# AIO-RF-v2-Sheet1.net
KiCad netlist of a schematic drawn in Altium Designer
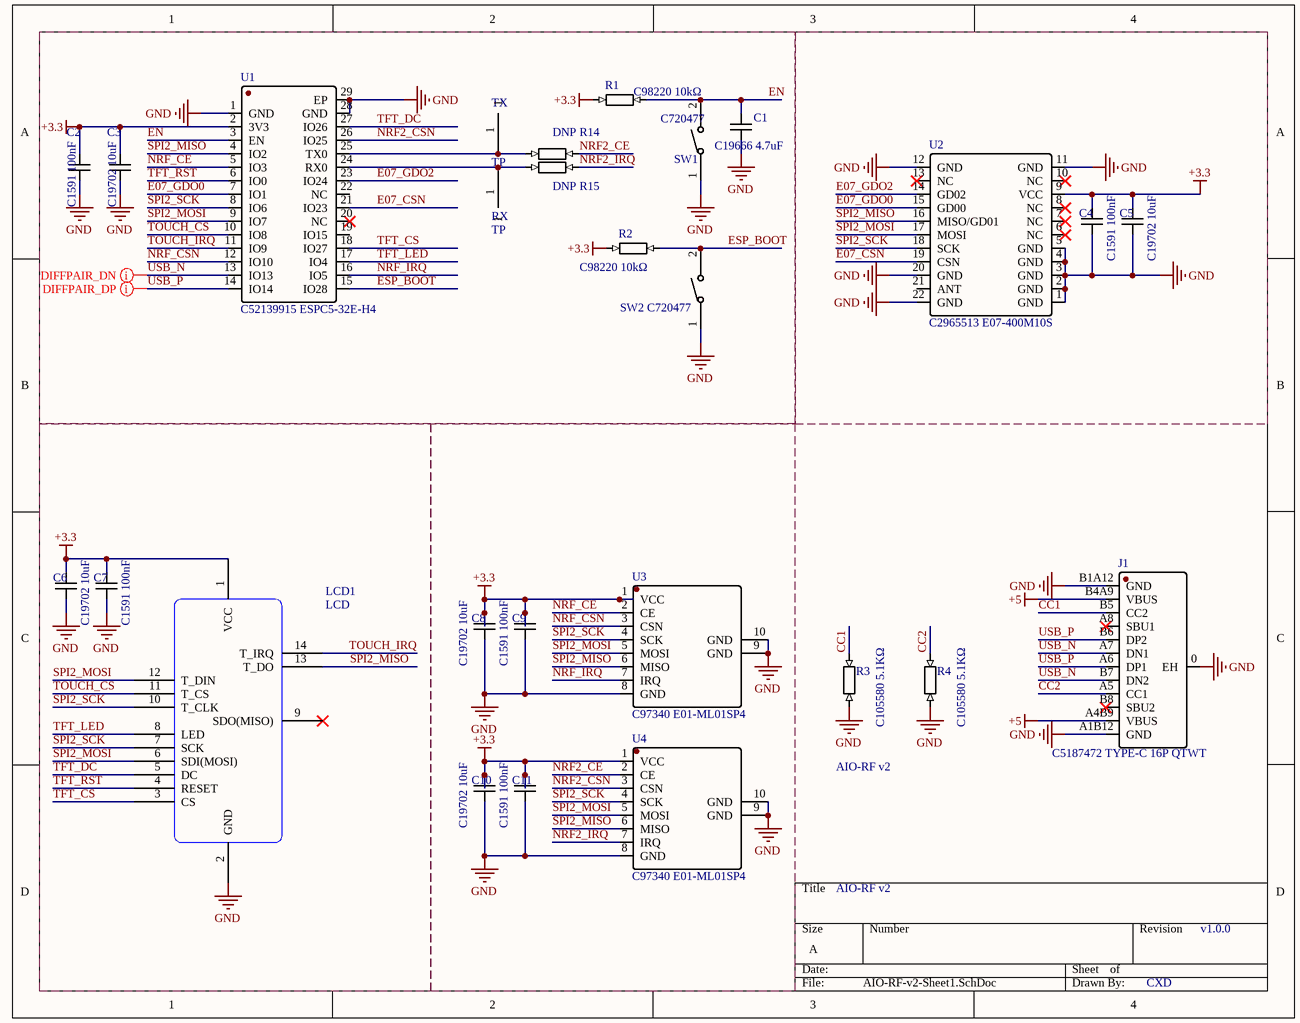
[diagram p0: AIO-RF-v2-Sheet1.SchDoc]

(export (version "E")
  (design (tool "Eeschema 10.0.6"))
  (components
    (comp (ref "C1")
      (value "C19666 4.7uF")
      (footprint "C19666")
      (description "4.7uF (475) ±10% 16V")
      (fields
        (field (name "LCSC PART NUMBER") "C19666")
        (field (name "MANUFACTURER") "SAMSUNG(三星)")
        (field (name "IMPORTED BY") "JLCAltiumImporter 0.3.1")
      )
      (libsource (lib "Schlib1") (part "C19666"))
    )
    (comp (ref "C2")
      (value "C1591 100nF")
      (footprint "C1591")
      (description "100nF (104) ±10% 50V")
      (fields
        (field (name "LCSC PART NUMBER") "C1591")
        (field (name "MANUFACTURER") "SAMSUNG(三星)")
        (field (name "IMPORTED BY") "JLCAltiumImporter 0.3.1")
      )
      (libsource (lib "Schlib1") (part "C1591"))
    )
    (comp (ref "C3")
      (value "C19702 10uF")
      (footprint "C19702")
      (fields
        (field (name "LCSC PART NUMBER") "C19702")
        (field (name "MANUFACTURER") "SAMSUNG(三星)")
        (field (name "MANUFACTURER PART NUMBER") "CL10A106KP8NNNC")
        (field (name "IMPORTED BY") "JLCAltiumImporter 0.3.1")
      )
      (libsource (lib "Schlib1") (part "C19702"))
    )
    (comp (ref "C4")
      (value "C1591 100nF")
      (footprint "C1591")
      (description "100nF (104) ±10% 50V")
      (fields
        (field (name "LCSC PART NUMBER") "C1591")
        (field (name "MANUFACTURER") "SAMSUNG(三星)")
        (field (name "IMPORTED BY") "JLCAltiumImporter 0.3.1")
      )
      (libsource (lib "Schlib1") (part "C1591"))
    )
    (comp (ref "C5")
      (value "C19702 10uF")
      (footprint "C19702")
      (fields
        (field (name "LCSC PART NUMBER") "C19702")
        (field (name "MANUFACTURER") "SAMSUNG(三星)")
        (field (name "MANUFACTURER PART NUMBER") "CL10A106KP8NNNC")
        (field (name "IMPORTED BY") "JLCAltiumImporter 0.3.1")
      )
      (libsource (lib "Schlib1") (part "C19702"))
    )
    (comp (ref "C6")
      (value "C19702 10uF")
      (footprint "C19702")
      (fields
        (field (name "LCSC PART NUMBER") "C19702")
        (field (name "MANUFACTURER") "SAMSUNG(三星)")
        (field (name "MANUFACTURER PART NUMBER") "CL10A106KP8NNNC")
        (field (name "IMPORTED BY") "JLCAltiumImporter 0.3.1")
      )
      (libsource (lib "Schlib1") (part "C19702"))
    )
    (comp (ref "C7")
      (value "C1591 100nF")
      (footprint "C1591")
      (description "100nF (104) ±10% 50V")
      (fields
        (field (name "LCSC PART NUMBER") "C1591")
        (field (name "MANUFACTURER") "SAMSUNG(三星)")
        (field (name "IMPORTED BY") "JLCAltiumImporter 0.3.1")
      )
      (libsource (lib "Schlib1") (part "C1591"))
    )
    (comp (ref "C8")
      (value "C19702 10uF")
      (footprint "C19702")
      (fields
        (field (name "LCSC PART NUMBER") "C19702")
        (field (name "MANUFACTURER") "SAMSUNG(三星)")
        (field (name "MANUFACTURER PART NUMBER") "CL10A106KP8NNNC")
        (field (name "IMPORTED BY") "JLCAltiumImporter 0.3.1")
      )
      (libsource (lib "Schlib1") (part "C19702"))
    )
    (comp (ref "C9")
      (value "C1591 100nF")
      (footprint "C1591")
      (description "100nF (104) ±10% 50V")
      (fields
        (field (name "LCSC PART NUMBER") "C1591")
        (field (name "MANUFACTURER") "SAMSUNG(三星)")
        (field (name "IMPORTED BY") "JLCAltiumImporter 0.3.1")
      )
      (libsource (lib "Schlib1") (part "C1591"))
    )
    (comp (ref "C10")
      (value "C19702 10uF")
      (footprint "C19702")
      (fields
        (field (name "LCSC PART NUMBER") "C19702")
        (field (name "MANUFACTURER") "SAMSUNG(三星)")
        (field (name "MANUFACTURER PART NUMBER") "CL10A106KP8NNNC")
        (field (name "IMPORTED BY") "JLCAltiumImporter 0.3.1")
      )
      (libsource (lib "Schlib1") (part "C19702"))
    )
    (comp (ref "C11")
      (value "C1591 100nF")
      (footprint "C1591")
      (description "100nF (104) ±10% 50V")
      (fields
        (field (name "LCSC PART NUMBER") "C1591")
        (field (name "MANUFACTURER") "SAMSUNG(三星)")
        (field (name "IMPORTED BY") "JLCAltiumImporter 0.3.1")
      )
      (libsource (lib "Schlib1") (part "C1591"))
    )
    (comp (ref "J1")
      (value "C5187472 TYPE-C 16P QTWT")
      (footprint "C5187472")
      (fields
        (field (name "LCSC PART NUMBER") "C5187472")
        (field (name "MANUFACTURER") "SHOU HAN(首韩)")
        (field (name "MANUFACTURER PART NUMBER") "TYPE-C 16P QTWT")
        (field (name "IMPORTED BY") "JLCAltiumImporter 0.2.3")
      )
      (libsource (lib "Schlib1") (part "C5187472"))
    )
    (comp (ref "LCD1") (value "LCD") (footprint "LCD") (libsource (lib "Schlib1") (part "LCD")))
    (comp (ref "R1")
      (value "C98220 10kΩ")
      (footprint "C98220")
      (fields
        (field (name "LCSC PART NUMBER") "C98220")
        (field (name "MANUFACTURER") "YAGEO(国巨)")
        (field (name "MANUFACTURER PART NUMBER") "RC0603FR-0710KL")
        (field (name "IMPORTED BY") "JLCAltiumImporter 0.3.1")
      )
      (libsource (lib "Schlib1") (part "C98220"))
    )
    (comp (ref "R2")
      (value "C98220 10kΩ")
      (footprint "C98220")
      (fields
        (field (name "LCSC PART NUMBER") "C98220")
        (field (name "MANUFACTURER") "YAGEO(国巨)")
        (field (name "MANUFACTURER PART NUMBER") "RC0603FR-0710KL")
        (field (name "IMPORTED BY") "JLCAltiumImporter 0.3.1")
      )
      (libsource (lib "Schlib1") (part "C98220"))
    )
    (comp (ref "R3")
      (value "C105580 5.1KΩ")
      (footprint "C105580")
      (fields
        (field (name "MANUFACTURER") "YAGEO(国巨)")
        (field (name "MANUFACTURER PART NUMBER") "RC0603FR-075K1L")
        (field (name "LCSC PART NUMBER") "C105580")
        (field (name "IMPORTED BY") "JLCAltiumImporter 0.3.1")
      )
      (libsource (lib "Schlib1") (part "C105580"))
    )
    (comp (ref "R4")
      (value "C105580 5.1KΩ")
      (footprint "C105580")
      (fields
        (field (name "MANUFACTURER") "YAGEO(国巨)")
        (field (name "MANUFACTURER PART NUMBER") "RC0603FR-075K1L")
        (field (name "LCSC PART NUMBER") "C105580")
        (field (name "IMPORTED BY") "JLCAltiumImporter 0.3.1")
      )
      (libsource (lib "Schlib1") (part "C105580"))
    )
    (comp (ref "R14")
      (value "DNP")
      (footprint "C98220")
      (fields
        (field (name "LCSC PART NUMBER") "C98220")
        (field (name "MANUFACTURER") "YAGEO(国巨)")
        (field (name "MANUFACTURER PART NUMBER") "RC0603FR-0710KL")
        (field (name "IMPORTED BY") "JLCAltiumImporter 0.3.1")
      )
      (libsource (lib "Schlib1") (part "C98220"))
    )
    (comp (ref "R15")
      (value "DNP")
      (footprint "C98220")
      (fields
        (field (name "LCSC PART NUMBER") "C98220")
        (field (name "MANUFACTURER") "YAGEO(国巨)")
        (field (name "MANUFACTURER PART NUMBER") "RC0603FR-0710KL")
        (field (name "IMPORTED BY") "JLCAltiumImporter 0.3.1")
      )
      (libsource (lib "Schlib1") (part "C98220"))
    )
    (comp (ref "RX") (value "TP") (footprint "TP") (libsource (lib "Schlib1") (part "TP")))
    (comp (ref "SW1")
      (value "C720477")
      (footprint "C720477")
      (fields
        (field (name "MANUFACTURER") "XUNPU(讯普)")
        (field (name "MANUFACTURER PART NUMBER") "TS-1088-AR02016")
        (field (name "IMPORTED BY") "JLCAltiumImporter 0.2.3")
      )
      (libsource (lib "Schlib1") (part "C720477"))
    )
    (comp (ref "SW2")
      (value "C720477")
      (footprint "C720477")
      (fields
        (field (name "MANUFACTURER") "XUNPU(讯普)")
        (field (name "MANUFACTURER PART NUMBER") "TS-1088-AR02016")
        (field (name "IMPORTED BY") "JLCAltiumImporter 0.2.3")
      )
      (libsource (lib "Schlib1") (part "C720477"))
    )
    (comp (ref "TX") (value "TP") (footprint "TP") (libsource (lib "Schlib1") (part "TP")))
    (comp (ref "U1")
      (value "C52139915 ESPC5-32E-H4")
      (footprint "C52139915")
      (fields
        (field (name "LCSC PART NUMBER") "C52139915")
        (field (name "MANUFACTURER") "DOIT(四博智联)")
        (field (name "MANUFACTURER PART NUMBER") "ESPC5-32E-H4")
        (field (name "IMPORTED BY") "JLCAltiumImporter 0.2.3")
      )
      (libsource (lib "Schlib1") (part "C52139915"))
    )
    (comp (ref "U2")
      (value "C2965513 E07-400M10S")
      (footprint "C2965513")
      (fields
        (field (name "LCSC PART NUMBER") "C2965513")
        (field (name "MANUFACTURER") "EBYTE(亿佰特)")
        (field (name "MANUFACTURER PART NUMBER") "E07-400M10S")
        (field (name "IMPORTED BY") "JLCAltiumImporter 0.2.3")
      )
      (libsource (lib "Schlib1") (part "C2965513"))
    )
    (comp (ref "U3")
      (value "C97340 E01-ML01SP4")
      (footprint "C97340")
      (fields
        (field (name "LCSC PART NUMBER") "C97340")
        (field (name "MANUFACTURER") "EBYTE(亿佰特)")
        (field (name "MANUFACTURER PART NUMBER") "E01-ML01SP4")
        (field (name "IMPORTED BY") "JLCAltiumImporter 0.2.3")
      )
      (libsource (lib "Schlib1") (part "C97340"))
    )
    (comp (ref "U4")
      (value "C97340 E01-ML01SP4")
      (footprint "C97340")
      (fields
        (field (name "LCSC PART NUMBER") "C97340")
        (field (name "MANUFACTURER") "EBYTE(亿佰特)")
        (field (name "MANUFACTURER PART NUMBER") "E01-ML01SP4")
        (field (name "IMPORTED BY") "JLCAltiumImporter 0.2.3")
      )
      (libsource (lib "Schlib1") (part "C97340"))
    )
  )
  (nets
    (net (code "1") (name "+3.3") (class "Default")
      (node (ref "C10") (pin "1") (pinfunction "1_1") (pintype "passive"))
      (node (ref "C11") (pin "1") (pinfunction "1_1") (pintype "passive"))
      (node (ref "C2") (pin "2") (pinfunction "2_2") (pintype "passive"))
      (node (ref "C3") (pin "2") (pinfunction "2_2") (pintype "passive"))
      (node (ref "C4") (pin "2") (pinfunction "2_2") (pintype "passive"))
      (node (ref "C5") (pin "2") (pinfunction "2_2") (pintype "passive"))
      (node (ref "C6") (pin "2") (pinfunction "2_2") (pintype "passive"))
      (node (ref "C7") (pin "2") (pinfunction "2_2") (pintype "passive"))
      (node (ref "C8") (pin "1") (pinfunction "1_1") (pintype "passive"))
      (node (ref "C9") (pin "1") (pinfunction "1_1") (pintype "passive"))
      (node (ref "LCD1") (pin "1") (pinfunction "VCC_1") (pintype "passive"))
      (node (ref "R1") (pin "1") (pinfunction "1_1") (pintype "input"))
      (node (ref "R2") (pin "1") (pinfunction "1_1") (pintype "input"))
      (node (ref "U1") (pin "2") (pinfunction "3V3_2") (pintype "passive"))
      (node (ref "U2") (pin "9") (pinfunction "VCC_9") (pintype "passive"))
      (node (ref "U3") (pin "1") (pinfunction "VCC_1") (pintype "passive"))
      (node (ref "U4") (pin "1") (pinfunction "VCC_1") (pintype "passive"))
    )
    (net (code "2") (name "+5") (class "Default")
      (node (ref "J1") (pin "A4B9") (pinfunction "VBUS_A4B9") (pintype "passive"))
      (node (ref "J1") (pin "B4A9") (pinfunction "VBUS_B4A9") (pintype "passive"))
    )
    (net (code "3") (name "/CC1") (class "Default")
      (node (ref "J1") (pin "B5") (pinfunction "CC2_B5") (pintype "passive"))
      (node (ref "R3") (pin "2") (pinfunction "2_2") (pintype "input"))
    )
    (net (code "4") (name "/CC2") (class "Default")
      (node (ref "J1") (pin "A5") (pinfunction "CC1_A5") (pintype "passive"))
      (node (ref "R4") (pin "2") (pinfunction "2_2") (pintype "input"))
    )
    (net (code "5") (name "/E07_CSN") (class "Default")
      (node (ref "U1") (pin "21") (pinfunction "IO23_21") (pintype "passive"))
      (node (ref "U2") (pin "19") (pinfunction "CSN_19") (pintype "passive"))
    )
    (net (code "6") (name "/E07_GDO0") (class "Default")
      (node (ref "U1") (pin "7") (pinfunction "IO1_7") (pintype "passive"))
      (node (ref "U2") (pin "15") (pinfunction "GD00_15") (pintype "passive"))
    )
    (net (code "7") (name "/E07_GDO2") (class "Default")
      (node (ref "U1") (pin "23") (pinfunction "IO24_23") (pintype "passive"))
      (node (ref "U2") (pin "14") (pinfunction "GD02_14") (pintype "passive"))
    )
    (net (code "8") (name "/EN") (class "Default")
      (node (ref "C1") (pin "1") (pinfunction "1_1") (pintype "passive"))
      (node (ref "R1") (pin "2") (pinfunction "2_2") (pintype "input"))
      (node (ref "SW1") (pin "2") (pinfunction "2_2") (pintype "passive"))
      (node (ref "U1") (pin "3") (pinfunction "EN_3") (pintype "passive"))
    )
    (net (code "9") (name "/ESP_BOOT") (class "Default")
      (node (ref "R2") (pin "2") (pinfunction "2_2") (pintype "input"))
      (node (ref "SW2") (pin "2") (pinfunction "2_2") (pintype "passive"))
      (node (ref "U1") (pin "15") (pinfunction "IO28_15") (pintype "passive"))
    )
    (net (code "10") (name "/NRF2_CE") (class "Default")
      (node (ref "R15") (pin "2") (pinfunction "2_2") (pintype "input"))
      (node (ref "U4") (pin "2") (pinfunction "CE_2") (pintype "passive"))
    )
    (net (code "11") (name "/NRF2_CSN") (class "Default")
      (node (ref "U1") (pin "26") (pinfunction "IO25_26") (pintype "passive"))
      (node (ref "U4") (pin "3") (pinfunction "CSN_3") (pintype "passive"))
    )
    (net (code "12") (name "/NRF2_IRQ") (class "Default")
      (node (ref "R14") (pin "2") (pinfunction "2_2") (pintype "input"))
      (node (ref "U4") (pin "7") (pinfunction "IRQ_7") (pintype "passive"))
    )
    (net (code "13") (name "/NRF_CE") (class "Default")
      (node (ref "U1") (pin "5") (pinfunction "IO3_5") (pintype "passive"))
      (node (ref "U3") (pin "2") (pinfunction "CE_2") (pintype "passive"))
    )
    (net (code "14") (name "/NRF_CSN") (class "Default")
      (node (ref "U1") (pin "12") (pinfunction "IO10_12") (pintype "passive"))
      (node (ref "U3") (pin "3") (pinfunction "CSN_3") (pintype "passive"))
    )
    (net (code "15") (name "/NRF_IRQ") (class "Default")
      (node (ref "U1") (pin "16") (pinfunction "IO5_16") (pintype "passive"))
      (node (ref "U3") (pin "7") (pinfunction "IRQ_7") (pintype "passive"))
    )
    (net (code "16") (name "/SPI2_MISO") (class "Default")
      (node (ref "LCD1") (pin "13") (pinfunction "T_DO_13") (pintype "passive"))
      (node (ref "U1") (pin "4") (pinfunction "IO2_4") (pintype "passive"))
      (node (ref "U2") (pin "16") (pinfunction "MISO/GD01_16") (pintype "passive"))
      (node (ref "U3") (pin "6") (pinfunction "MISO_6") (pintype "passive"))
      (node (ref "U4") (pin "6") (pinfunction "MISO_6") (pintype "passive"))
    )
    (net (code "17") (name "/SPI2_MOSI") (class "Default")
      (node (ref "LCD1") (pin "12") (pinfunction "T_DIN_12") (pintype "passive"))
      (node (ref "LCD1") (pin "6") (pinfunction "SDI(MOSI)_6") (pintype "passive"))
      (node (ref "U1") (pin "9") (pinfunction "IO7_9") (pintype "passive"))
      (node (ref "U2") (pin "17") (pinfunction "MOSI_17") (pintype "passive"))
      (node (ref "U3") (pin "5") (pinfunction "MOSI_5") (pintype "passive"))
      (node (ref "U4") (pin "5") (pinfunction "MOSI_5") (pintype "passive"))
    )
    (net (code "18") (name "/SPI2_SCK") (class "Default")
      (node (ref "LCD1") (pin "10") (pinfunction "T_CLK_10") (pintype "passive"))
      (node (ref "LCD1") (pin "7") (pinfunction "SCK_7") (pintype "passive"))
      (node (ref "U1") (pin "8") (pinfunction "IO6_8") (pintype "passive"))
      (node (ref "U2") (pin "18") (pinfunction "SCK_18") (pintype "passive"))
      (node (ref "U3") (pin "4") (pinfunction "SCK_4") (pintype "passive"))
      (node (ref "U4") (pin "4") (pinfunction "SCK_4") (pintype "passive"))
    )
    (net (code "19") (name "/TFT_CS") (class "Default")
      (node (ref "LCD1") (pin "3") (pinfunction "CS_3") (pintype "passive"))
      (node (ref "U1") (pin "18") (pinfunction "IO27_18") (pintype "passive"))
    )
    (net (code "20") (name "/TFT_DC") (class "Default")
      (node (ref "LCD1") (pin "5") (pinfunction "DC_5") (pintype "passive"))
      (node (ref "U1") (pin "27") (pinfunction "IO26_27") (pintype "passive"))
    )
    (net (code "21") (name "/TFT_LED") (class "Default")
      (node (ref "LCD1") (pin "8") (pinfunction "LED_8") (pintype "passive"))
      (node (ref "U1") (pin "17") (pinfunction "IO4_17") (pintype "passive"))
    )
    (net (code "22") (name "/TFT_RST") (class "Default")
      (node (ref "LCD1") (pin "4") (pinfunction "RESET_4") (pintype "passive"))
      (node (ref "U1") (pin "6") (pinfunction "IO0_6") (pintype "passive"))
    )
    (net (code "23") (name "/TOUCH_CS") (class "Default")
      (node (ref "LCD1") (pin "11") (pinfunction "T_CS_11") (pintype "passive"))
      (node (ref "U1") (pin "10") (pinfunction "IO8_10") (pintype "passive"))
    )
    (net (code "24") (name "/TOUCH_IRQ") (class "Default")
      (node (ref "LCD1") (pin "14") (pinfunction "T_IRQ_14") (pintype "passive"))
      (node (ref "U1") (pin "11") (pinfunction "IO9_11") (pintype "passive"))
    )
    (net (code "25") (name "/USB_N") (class "Default")
      (node (ref "J1") (pin "A7") (pinfunction "DN1_A7") (pintype "passive"))
      (node (ref "J1") (pin "B7") (pinfunction "DN2_B7") (pintype "passive"))
      (node (ref "U1") (pin "13") (pinfunction "IO13_13") (pintype "passive"))
    )
    (net (code "26") (name "/USB_P") (class "Default")
      (node (ref "J1") (pin "A6") (pinfunction "DP1_A6") (pintype "passive"))
      (node (ref "J1") (pin "B6") (pinfunction "DP2_B6") (pintype "passive"))
      (node (ref "U1") (pin "14") (pinfunction "IO14_14") (pintype "passive"))
    )
    (net (code "27") (name "GND") (class "Default")
      (node (ref "C1") (pin "2") (pinfunction "2_2") (pintype "passive"))
      (node (ref "C10") (pin "2") (pinfunction "2_2") (pintype "passive"))
      (node (ref "C11") (pin "2") (pinfunction "2_2") (pintype "passive"))
      (node (ref "C2") (pin "1") (pinfunction "1_1") (pintype "passive"))
      (node (ref "C3") (pin "1") (pinfunction "1_1") (pintype "passive"))
      (node (ref "C4") (pin "1") (pinfunction "1_1") (pintype "passive"))
      (node (ref "C5") (pin "1") (pinfunction "1_1") (pintype "passive"))
      (node (ref "C6") (pin "1") (pinfunction "1_1") (pintype "passive"))
      (node (ref "C7") (pin "1") (pinfunction "1_1") (pintype "passive"))
      (node (ref "C8") (pin "2") (pinfunction "2_2") (pintype "passive"))
      (node (ref "C9") (pin "2") (pinfunction "2_2") (pintype "passive"))
      (node (ref "J1") (pin "0") (pinfunction "EH_0") (pintype "passive"))
      (node (ref "J1") (pin "A1B12") (pinfunction "GND_A1B12") (pintype "passive"))
      (node (ref "J1") (pin "B1A12") (pinfunction "GND_B1A12") (pintype "passive"))
      (node (ref "LCD1") (pin "2") (pinfunction "GND_2") (pintype "passive"))
      (node (ref "R3") (pin "1") (pinfunction "1_1") (pintype "input"))
      (node (ref "R4") (pin "1") (pinfunction "1_1") (pintype "input"))
      (node (ref "SW1") (pin "1") (pinfunction "1_1") (pintype "passive"))
      (node (ref "SW2") (pin "1") (pinfunction "1_1") (pintype "passive"))
      (node (ref "U1") (pin "1") (pinfunction "GND_1") (pintype "passive"))
      (node (ref "U1") (pin "28") (pinfunction "GND_28") (pintype "passive"))
      (node (ref "U1") (pin "29") (pinfunction "EP_29") (pintype "passive"))
      (node (ref "U2") (pin "1") (pinfunction "GND_1") (pintype "passive"))
      (node (ref "U2") (pin "11") (pinfunction "GND_11") (pintype "passive"))
      (node (ref "U2") (pin "12") (pinfunction "GND_12") (pintype "passive"))
      (node (ref "U2") (pin "2") (pinfunction "GND_2") (pintype "passive"))
      (node (ref "U2") (pin "20") (pinfunction "GND_20") (pintype "passive"))
      (node (ref "U2") (pin "22") (pinfunction "GND_22") (pintype "passive"))
      (node (ref "U2") (pin "3") (pinfunction "GND_3") (pintype "passive"))
      (node (ref "U2") (pin "4") (pinfunction "GND_4") (pintype "passive"))
      (node (ref "U2") (pin "5") (pinfunction "GND_5") (pintype "passive"))
      (node (ref "U3") (pin "10") (pinfunction "GND_10") (pintype "passive"))
      (node (ref "U3") (pin "8") (pinfunction "GND_8") (pintype "passive"))
      (node (ref "U3") (pin "9") (pinfunction "GND_9") (pintype "passive"))
      (node (ref "U4") (pin "10") (pinfunction "GND_10") (pintype "passive"))
      (node (ref "U4") (pin "8") (pinfunction "GND_8") (pintype "passive"))
      (node (ref "U4") (pin "9") (pinfunction "GND_9") (pintype "passive"))
    )
    (net (code "28") (name "Net-(U1-RX0)") (class "Default")
      (node (ref "R14") (pin "1") (pinfunction "1_1") (pintype "input"))
      (node (ref "RX") (pin "1") (pinfunction "1_1") (pintype "passive"))
      (node (ref "U1") (pin "24") (pinfunction "RX0_24") (pintype "passive"))
    )
    (net (code "29") (name "Net-(U1-TX0)") (class "Default")
      (node (ref "R15") (pin "1") (pinfunction "1_1") (pintype "input"))
      (node (ref "TX") (pin "1") (pinfunction "1_1") (pintype "passive"))
      (node (ref "U1") (pin "25") (pinfunction "TX0_25") (pintype "passive"))
    )
    (net (code "30") (name "unconnected-(J1-SBU1-PadA8)") (class "Default")
      (node (ref "J1") (pin "A8") (pinfunction "SBU1_A8") (pintype "passive+no_connect"))
    )
    (net (code "31") (name "unconnected-(J1-SBU2-PadB8)") (class "Default")
      (node (ref "J1") (pin "B8") (pinfunction "SBU2_B8") (pintype "passive+no_connect"))
    )
    (net (code "32") (name "unconnected-(LCD1-SDO(MISO)-Pad9)") (class "Default")
      (node (ref "LCD1") (pin "9") (pinfunction "SDO(MISO)_9") (pintype "passive+no_connect"))
    )
    (net (code "33") (name "unconnected-(U1-IO15-Pad19)") (class "Default")
      (node (ref "U1") (pin "19") (pinfunction "IO15_19") (pintype "passive"))
    )
    (net (code "34") (name "unconnected-(U1-NC-Pad20)") (class "Default")
      (node (ref "U1") (pin "20") (pinfunction "NC_20") (pintype "passive+no_connect"))
    )
    (net (code "35") (name "unconnected-(U1-NC-Pad22)") (class "Default")
      (node (ref "U1") (pin "22") (pinfunction "NC_22") (pintype "passive"))
    )
    (net (code "36") (name "unconnected-(U2-ANT-Pad21)") (class "Default")
      (node (ref "U2") (pin "21") (pinfunction "ANT_21") (pintype "passive"))
    )
    (net (code "37") (name "unconnected-(U2-NC-Pad6)") (class "Default")
      (node (ref "U2") (pin "6") (pinfunction "NC_6") (pintype "passive+no_connect"))
    )
    (net (code "38") (name "unconnected-(U2-NC-Pad7)") (class "Default")
      (node (ref "U2") (pin "7") (pinfunction "NC_7") (pintype "passive+no_connect"))
    )
    (net (code "39") (name "unconnected-(U2-NC-Pad8)") (class "Default")
      (node (ref "U2") (pin "8") (pinfunction "NC_8") (pintype "passive+no_connect"))
    )
    (net (code "40") (name "unconnected-(U2-NC-Pad10)") (class "Default")
      (node (ref "U2") (pin "10") (pinfunction "NC_10") (pintype "passive+no_connect"))
    )
    (net (code "41") (name "unconnected-(U2-NC-Pad13)") (class "Default")
      (node (ref "U2") (pin "13") (pinfunction "NC_13") (pintype "passive+no_connect"))
    )
  )
)
